# NES.net
KiCad netlist of a schematic drawn in EAGLE
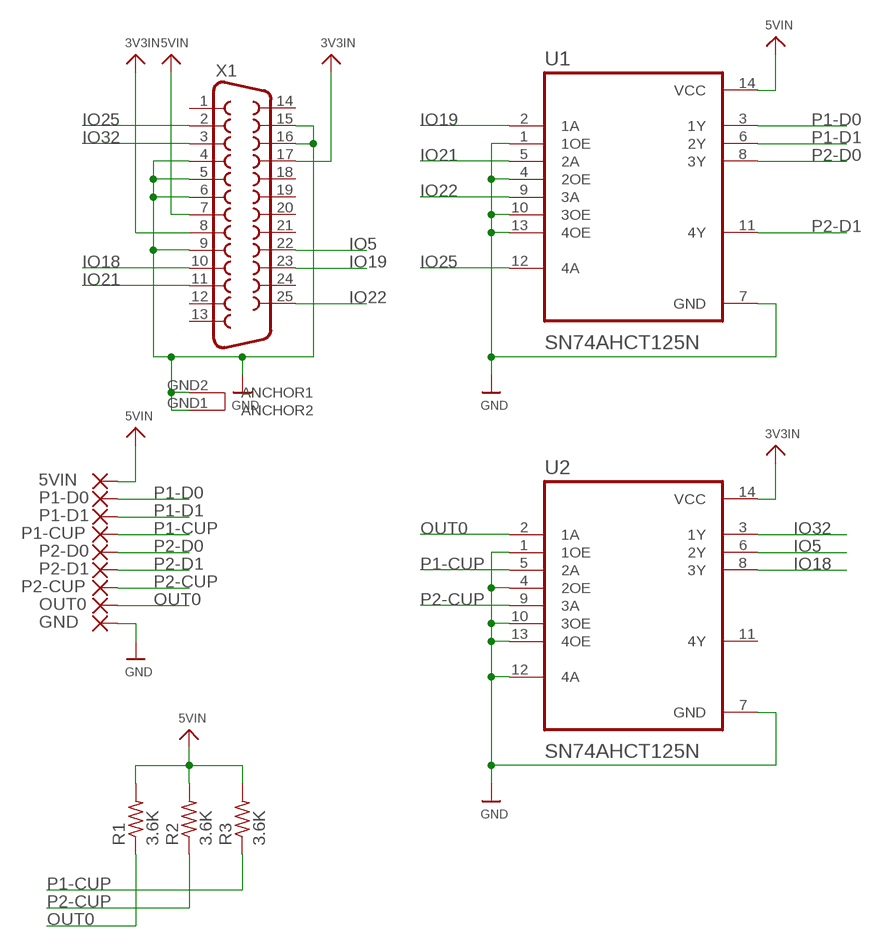
[diagram p0: schematic, sheet 1]

(export (version "E")
  (design (tool "Eeschema 10.0.6"))
  (components
    (comp (ref "5VIN")
      (value "SMD5")
      (footprint "eagle-import:SMD2,54-5,08")
      (libsource (lib "eagle-import") (part "SMD5"))
    )
    (comp (ref "GND")
      (value "SMD5")
      (footprint "eagle-import:SMD2,54-5,08")
      (libsource (lib "eagle-import") (part "SMD5"))
    )
    (comp (ref "OUT0")
      (value "SMD5")
      (footprint "eagle-import:SMD2,54-5,08")
      (libsource (lib "eagle-import") (part "SMD5"))
    )
    (comp (ref "P1-CUP")
      (value "SMD5")
      (footprint "eagle-import:SMD2,54-5,08")
      (libsource (lib "eagle-import") (part "SMD5"))
    )
    (comp (ref "P1-D0")
      (value "SMD5")
      (footprint "eagle-import:SMD2,54-5,08")
      (libsource (lib "eagle-import") (part "SMD5"))
    )
    (comp (ref "P1-D1")
      (value "SMD5")
      (footprint "eagle-import:SMD2,54-5,08")
      (libsource (lib "eagle-import") (part "SMD5"))
    )
    (comp (ref "P2-CUP")
      (value "SMD5")
      (footprint "eagle-import:SMD2,54-5,08")
      (libsource (lib "eagle-import") (part "SMD5"))
    )
    (comp (ref "P2-D0")
      (value "SMD5")
      (footprint "eagle-import:SMD2,54-5,08")
      (libsource (lib "eagle-import") (part "SMD5"))
    )
    (comp (ref "P2-D1")
      (value "SMD5")
      (footprint "eagle-import:SMD2,54-5,08")
      (libsource (lib "eagle-import") (part "SMD5"))
    )
    (comp (ref "R1")
      (value "3.6K")
      (footprint "eagle-import:R1206")
      (libsource (lib "eagle-import") (part "R-US_R1206"))
    )
    (comp (ref "R2")
      (value "3.6K")
      (footprint "eagle-import:R1206")
      (libsource (lib "eagle-import") (part "R-US_R1206"))
    )
    (comp (ref "R3")
      (value "3.6K")
      (footprint "eagle-import:R1206")
      (libsource (lib "eagle-import") (part "R-US_R1206"))
    )
    (comp (ref "U1")
      (value "SN74AHCT125N")
      (footprint "eagle-import:DIP794W45P254L1969H508Q14")
      (fields (field (name "MF") "Texas Instruments"))
      (libsource (lib "eagle-import") (part "SN74AHCT125N"))
    )
    (comp (ref "U2")
      (value "SN74AHCT125N")
      (footprint "eagle-import:DIP794W45P254L1969H508Q14")
      (fields (field (name "MF") "Texas Instruments"))
      (libsource (lib "eagle-import") (part "SN74AHCT125N"))
    )
    (comp (ref "X1")
      (value "DB25_FEMALEHP")
      (footprint "eagle-import:F25HP")
      (libsource (lib "eagle-import") (part "DB25_FEMALEHP"))
    )
  )
  (nets
    (net (code "1") (name "/IO5") (class "Default")
      (node (ref "U2") (pin "6") (pinfunction "2Y_6") (pintype "output"))
      (node (ref "X1") (pin "22") (pinfunction "22_22") (pintype "passive"))
    )
    (net (code "2") (name "/IO18") (class "Default")
      (node (ref "U2") (pin "8") (pinfunction "3Y_8") (pintype "output"))
      (node (ref "X1") (pin "10") (pinfunction "10_10") (pintype "passive"))
    )
    (net (code "3") (name "/IO19") (class "Default")
      (node (ref "U1") (pin "2") (pinfunction "1A_2") (pintype "input"))
      (node (ref "X1") (pin "23") (pinfunction "23_23") (pintype "passive"))
    )
    (net (code "4") (name "/IO21") (class "Default")
      (node (ref "U1") (pin "5") (pinfunction "2A_5") (pintype "input"))
      (node (ref "X1") (pin "11") (pinfunction "11_11") (pintype "passive"))
    )
    (net (code "5") (name "/IO22") (class "Default")
      (node (ref "U1") (pin "9") (pinfunction "3A_9") (pintype "input"))
      (node (ref "X1") (pin "25") (pinfunction "25_25") (pintype "passive"))
    )
    (net (code "6") (name "/IO25") (class "Default")
      (node (ref "U1") (pin "12") (pinfunction "4A_12") (pintype "bidirectional"))
      (node (ref "X1") (pin "2") (pinfunction "2_2") (pintype "passive"))
    )
    (net (code "7") (name "/IO32") (class "Default")
      (node (ref "U2") (pin "3") (pinfunction "1Y_3") (pintype "output"))
      (node (ref "X1") (pin "3") (pinfunction "3_3") (pintype "passive"))
    )
    (net (code "8") (name "/OUT0") (class "Default")
      (node (ref "OUT0") (pin "1") (pinfunction "P_1") (pintype "passive"))
      (node (ref "R1") (pin "1") (pinfunction "1_1") (pintype "passive"))
      (node (ref "U2") (pin "2") (pinfunction "1A_2") (pintype "input"))
    )
    (net (code "9") (name "/P1-CUP") (class "Default")
      (node (ref "P1-CUP") (pin "1") (pinfunction "P_1") (pintype "passive"))
      (node (ref "R3") (pin "1") (pinfunction "1_1") (pintype "passive"))
      (node (ref "U2") (pin "5") (pinfunction "2A_5") (pintype "input"))
    )
    (net (code "10") (name "/P1-D0") (class "Default")
      (node (ref "P1-D0") (pin "1") (pinfunction "P_1") (pintype "passive"))
      (node (ref "U1") (pin "3") (pinfunction "1Y_3") (pintype "output"))
    )
    (net (code "11") (name "/P1-D1") (class "Default")
      (node (ref "P1-D1") (pin "1") (pinfunction "P_1") (pintype "passive"))
      (node (ref "U1") (pin "6") (pinfunction "2Y_6") (pintype "output"))
    )
    (net (code "12") (name "/P2-CUP") (class "Default")
      (node (ref "P2-CUP") (pin "1") (pinfunction "P_1") (pintype "passive"))
      (node (ref "R2") (pin "1") (pinfunction "1_1") (pintype "passive"))
      (node (ref "U2") (pin "9") (pinfunction "3A_9") (pintype "input"))
    )
    (net (code "13") (name "/P2-D0") (class "Default")
      (node (ref "P2-D0") (pin "1") (pinfunction "P_1") (pintype "passive"))
      (node (ref "U1") (pin "8") (pinfunction "3Y_8") (pintype "output"))
    )
    (net (code "14") (name "/P2-D1") (class "Default")
      (node (ref "P2-D1") (pin "1") (pinfunction "P_1") (pintype "passive"))
      (node (ref "U1") (pin "11") (pinfunction "4Y_11") (pintype "output"))
    )
    (net (code "15") (name "3V3IN") (class "Default")
      (node (ref "U2") (pin "14") (pinfunction "VCC_14") (pintype "power_in"))
      (node (ref "X1") (pin "17") (pinfunction "17_17") (pintype "passive"))
      (node (ref "X1") (pin "8") (pinfunction "8_8") (pintype "passive"))
    )
    (net (code "16") (name "5VIN") (class "Default")
      (node (ref "5VIN") (pin "1") (pinfunction "P_1") (pintype "passive"))
      (node (ref "R1") (pin "2") (pinfunction "2_2") (pintype "passive"))
      (node (ref "R2") (pin "2") (pinfunction "2_2") (pintype "passive"))
      (node (ref "R3") (pin "2") (pinfunction "2_2") (pintype "passive"))
      (node (ref "U1") (pin "14") (pinfunction "VCC_14") (pintype "power_in"))
      (node (ref "X1") (pin "7") (pinfunction "7_7") (pintype "passive"))
    )
    (net (code "17") (name "GND") (class "Default")
      (node (ref "GND") (pin "1") (pinfunction "P_1") (pintype "passive"))
      (node (ref "U1") (pin "1") (pinfunction "1OE_1") (pintype "input"))
      (node (ref "U1") (pin "10") (pinfunction "3OE_10") (pintype "input"))
      (node (ref "U1") (pin "13") (pinfunction "4OE_13") (pintype "input"))
      (node (ref "U1") (pin "4") (pinfunction "2OE_4") (pintype "input"))
      (node (ref "U1") (pin "7") (pinfunction "GND_7") (pintype "power_in"))
      (node (ref "U2") (pin "1") (pinfunction "1OE_1") (pintype "input"))
      (node (ref "U2") (pin "10") (pinfunction "3OE_10") (pintype "input"))
      (node (ref "U2") (pin "12") (pinfunction "4A_12") (pintype "bidirectional"))
      (node (ref "U2") (pin "13") (pinfunction "4OE_13") (pintype "input"))
      (node (ref "U2") (pin "4") (pinfunction "2OE_4") (pintype "input"))
      (node (ref "U2") (pin "7") (pinfunction "GND_7") (pintype "power_in"))
      (node (ref "X1") (pin "15") (pinfunction "15_15") (pintype "passive"))
      (node (ref "X1") (pin "16") (pinfunction "16_16") (pintype "passive"))
      (node (ref "X1") (pin "4") (pinfunction "4_4") (pintype "passive"))
      (node (ref "X1") (pin "5") (pinfunction "5_5") (pintype "passive"))
      (node (ref "X1") (pin "6") (pinfunction "6_6") (pintype "passive"))
      (node (ref "X1") (pin "9") (pinfunction "9_9") (pintype "passive"))
      (node (ref "X1") (pin "GND1") (pinfunction "ANCHOR2_GND1") (pintype "bidirectional"))
      (node (ref "X1") (pin "GND2") (pinfunction "ANCHOR1_GND2") (pintype "bidirectional"))
    )
    (net (code "18") (name "unconnected-(U2-4Y-Pad11)") (class "Default")
      (node (ref "U2") (pin "11") (pinfunction "4Y_11") (pintype "output"))
    )
    (net (code "19") (name "unconnected-(X1-Pad1)") (class "Default")
      (node (ref "X1") (pin "1") (pinfunction "1_1") (pintype "passive"))
    )
    (net (code "20") (name "unconnected-(X1-Pad12)") (class "Default")
      (node (ref "X1") (pin "12") (pinfunction "12_12") (pintype "passive"))
    )
    (net (code "21") (name "unconnected-(X1-Pad13)") (class "Default")
      (node (ref "X1") (pin "13") (pinfunction "13_13") (pintype "passive"))
    )
    (net (code "22") (name "unconnected-(X1-Pad14)") (class "Default")
      (node (ref "X1") (pin "14") (pinfunction "14_14") (pintype "passive"))
    )
    (net (code "23") (name "unconnected-(X1-Pad18)") (class "Default")
      (node (ref "X1") (pin "18") (pinfunction "18_18") (pintype "passive"))
    )
    (net (code "24") (name "unconnected-(X1-Pad19)") (class "Default")
      (node (ref "X1") (pin "19") (pinfunction "19_19") (pintype "passive"))
    )
    (net (code "25") (name "unconnected-(X1-Pad20)") (class "Default")
      (node (ref "X1") (pin "20") (pinfunction "20_20") (pintype "passive"))
    )
    (net (code "26") (name "unconnected-(X1-Pad21)") (class "Default")
      (node (ref "X1") (pin "21") (pinfunction "21_21") (pintype "passive"))
    )
    (net (code "27") (name "unconnected-(X1-Pad24)") (class "Default")
      (node (ref "X1") (pin "24") (pinfunction "24_24") (pintype "passive"))
    )
  )
)
